# FOC_BOARD.net
KiCad netlist of a schematic drawn in Altium Designer
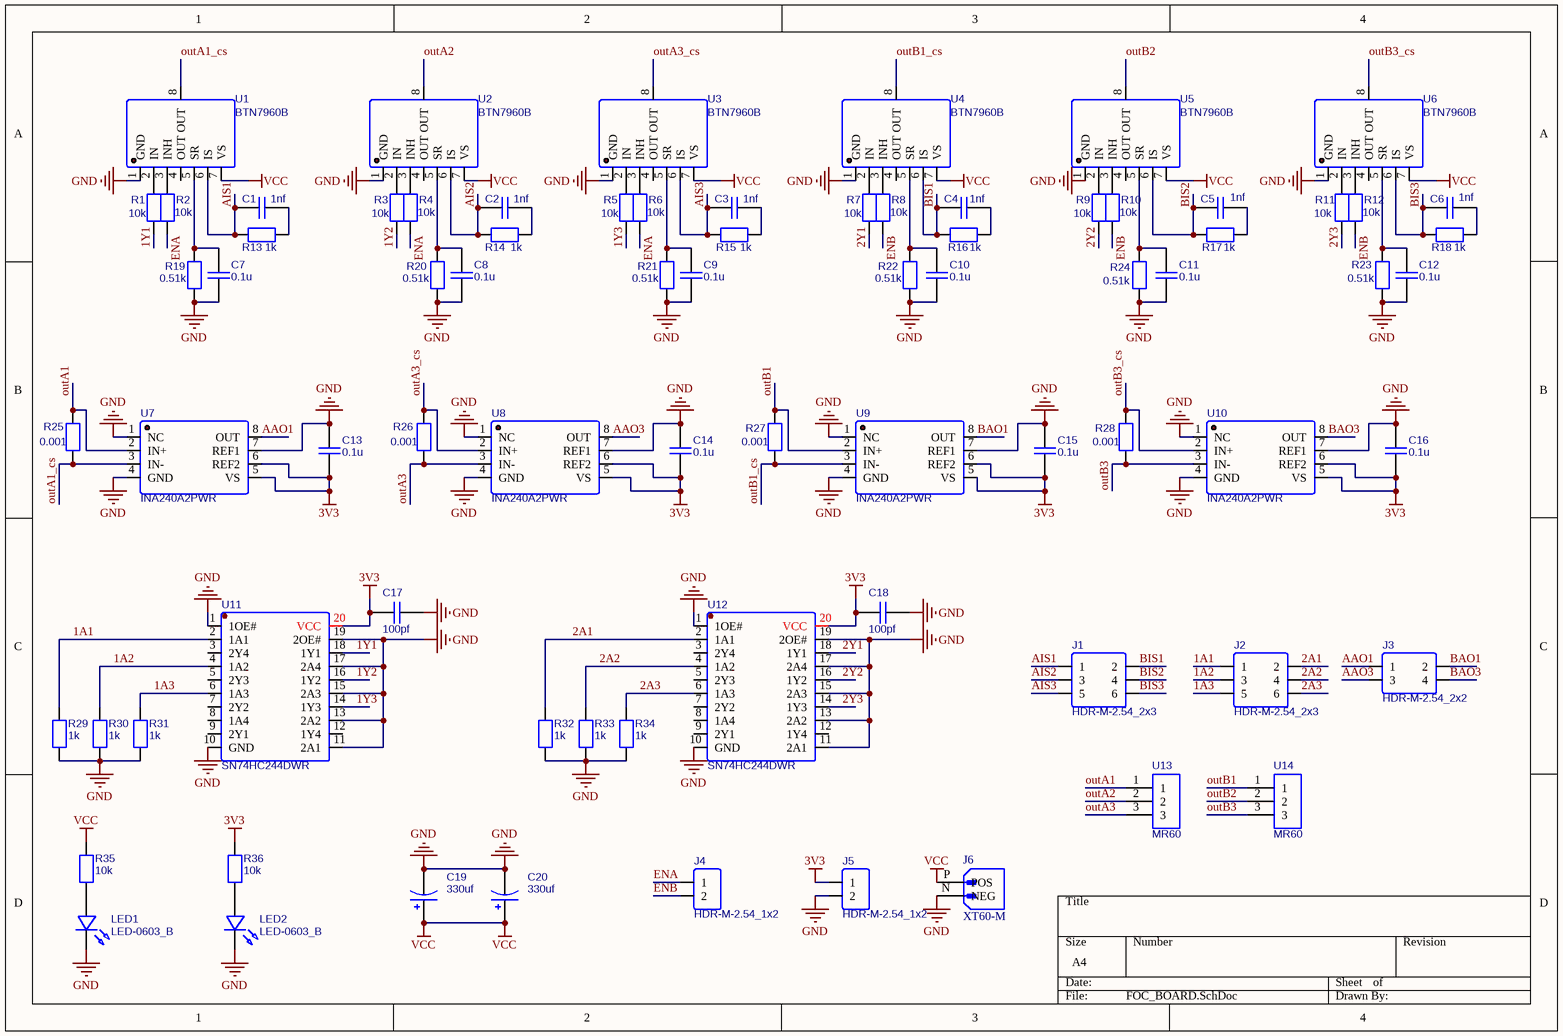
[diagram p0: FOC_BOARD.SchDoc]

(export (version "E")
  (design (tool "Eeschema 10.0.6"))
  (components
    (comp (ref "C1")
      (value "1nf")
      (footprint "C0603")
      (fields (field (name "CONTRIBUTOR") "LCEDA_Lib"))
      (libsource (lib "FOC_BOARD") (part "1nf"))
    )
    (comp (ref "C2")
      (value "1nf")
      (footprint "C0603")
      (fields (field (name "CONTRIBUTOR") "LCEDA_Lib"))
      (libsource (lib "FOC_BOARD") (part "1nf"))
    )
    (comp (ref "C3")
      (value "1nf")
      (footprint "C0603")
      (fields (field (name "CONTRIBUTOR") "LCEDA_Lib"))
      (libsource (lib "FOC_BOARD") (part "1nf"))
    )
    (comp (ref "C4")
      (value "1nf")
      (footprint "C0603")
      (fields (field (name "CONTRIBUTOR") "LCEDA_Lib"))
      (libsource (lib "FOC_BOARD") (part "1nf"))
    )
    (comp (ref "C5")
      (value "1nf")
      (footprint "C0603")
      (fields (field (name "CONTRIBUTOR") "LCEDA_Lib"))
      (libsource (lib "FOC_BOARD") (part "1nf"))
    )
    (comp (ref "C6")
      (value "1nf")
      (footprint "C0603")
      (fields (field (name "CONTRIBUTOR") "LCEDA_Lib"))
      (libsource (lib "FOC_BOARD") (part "1nf"))
    )
    (comp (ref "C7")
      (value "0.1u")
      (footprint "C0603")
      (fields (field (name "CONTRIBUTOR") "LCEDA_Lib"))
      (libsource (lib "FOC_BOARD") (part "0.1u"))
    )
    (comp (ref "C8")
      (value "0.1u")
      (footprint "C0603")
      (fields (field (name "CONTRIBUTOR") "LCEDA_Lib"))
      (libsource (lib "FOC_BOARD") (part "0.1u"))
    )
    (comp (ref "C9")
      (value "0.1u")
      (footprint "C0603")
      (fields (field (name "CONTRIBUTOR") "LCEDA_Lib"))
      (libsource (lib "FOC_BOARD") (part "0.1u"))
    )
    (comp (ref "C10")
      (value "0.1u")
      (footprint "C0603")
      (fields (field (name "CONTRIBUTOR") "LCEDA_Lib"))
      (libsource (lib "FOC_BOARD") (part "0.1u"))
    )
    (comp (ref "C11")
      (value "0.1u")
      (footprint "C0603")
      (fields (field (name "CONTRIBUTOR") "LCEDA_Lib"))
      (libsource (lib "FOC_BOARD") (part "0.1u"))
    )
    (comp (ref "C12")
      (value "0.1u")
      (footprint "C0603")
      (fields (field (name "CONTRIBUTOR") "LCEDA_Lib"))
      (libsource (lib "FOC_BOARD") (part "0.1u"))
    )
    (comp (ref "C13")
      (value "0.1u")
      (footprint "C0603")
      (fields (field (name "CONTRIBUTOR") "LCEDA_Lib"))
      (libsource (lib "FOC_BOARD") (part "0.1u"))
    )
    (comp (ref "C14")
      (value "0.1u")
      (footprint "C0603")
      (fields (field (name "CONTRIBUTOR") "LCEDA_Lib"))
      (libsource (lib "FOC_BOARD") (part "0.1u"))
    )
    (comp (ref "C15")
      (value "0.1u")
      (footprint "C0603")
      (fields (field (name "CONTRIBUTOR") "LCEDA_Lib"))
      (libsource (lib "FOC_BOARD") (part "0.1u"))
    )
    (comp (ref "C16")
      (value "0.1u")
      (footprint "C0603")
      (fields (field (name "CONTRIBUTOR") "LCEDA_Lib"))
      (libsource (lib "FOC_BOARD") (part "0.1u"))
    )
    (comp (ref "C17")
      (value "100pf")
      (footprint "C0603")
      (fields (field (name "CONTRIBUTOR") "LCEDA_Lib"))
      (libsource (lib "FOC_BOARD") (part "100pf"))
    )
    (comp (ref "C18")
      (value "100pf")
      (footprint "C0603")
      (fields (field (name "CONTRIBUTOR") "LCEDA_Lib"))
      (libsource (lib "FOC_BOARD") (part "100pf"))
    )
    (comp (ref "C19")
      (value "330uf")
      (footprint "CAP-T-10*10.5")
      (fields (field (name "CONTRIBUTOR") "LCEDA_Lib"))
      (libsource (lib "FOC_BOARD") (part "330uf"))
    )
    (comp (ref "C20")
      (value "330uf")
      (footprint "CAP-T-10*10.5")
      (fields (field (name "CONTRIBUTOR") "LCEDA_Lib"))
      (libsource (lib "FOC_BOARD") (part "330uf"))
    )
    (comp (ref "J1")
      (value "HDR-M-2.54_2x3")
      (footprint "HDR-M-2.54_2X3")
      (fields (field (name "BOM_SUPPLIER PART") "C65114") (field (name "CONTRIBUTOR") "LCEDA_Lib"))
      (libsource (lib "FOC_BOARD") (part "HDR-M-2.54_2x3"))
    )
    (comp (ref "J2")
      (value "HDR-M-2.54_2x3")
      (footprint "HDR-M-2.54_2X3")
      (fields (field (name "BOM_SUPPLIER PART") "C65114") (field (name "CONTRIBUTOR") "LCEDA_Lib"))
      (libsource (lib "FOC_BOARD") (part "HDR-M-2.54_2x3"))
    )
    (comp (ref "J3")
      (value "HDR-M-2.54_2x2")
      (footprint "HDR-M-2.54_2X2")
      (fields (field (name "BOM_SUPPLIER PART") "C66690") (field (name "CONTRIBUTOR") "LCEDA_Lib"))
      (libsource (lib "FOC_BOARD") (part "HDR-M-2.54_2x2"))
    )
    (comp (ref "J4")
      (value "HDR-M-2.54_1x2")
      (footprint "HDR-M-2.54_1X2")
      (fields (field (name "BOM_SUPPLIER PART") "C124375") (field (name "CONTRIBUTOR") "LCEDA_Lib"))
      (libsource (lib "FOC_BOARD") (part "HDR-M-2.54_1x2"))
    )
    (comp (ref "J5")
      (value "HDR-M-2.54_1x2")
      (footprint "HDR-M-2.54_1X2")
      (fields (field (name "BOM_SUPPLIER PART") "C124375") (field (name "CONTRIBUTOR") "LCEDA_Lib"))
      (libsource (lib "FOC_BOARD") (part "HDR-M-2.54_1x2"))
    )
    (comp (ref "J6")
      (value "XT60-M")
      (footprint "AMASS_XT60-M")
      (description "Plug; DC supply; XT60; male; PIN: 2; for cable; soldered; 30A; 500V")
      (fields (field (name "MF") "AMASS"))
      (libsource (lib "FOC_BOARD") (part "XT60-M"))
    )
    (comp (ref "LED1")
      (value "LED-0603_B")
      (footprint "LED0603_BLUE")
      (fields
        (field (name "BOM_MANUFACTURER PART") "19-217/BHC-ZL1M2RY/3T")
        (field (name "BOM_SUPPLIER PART") "C72041")
        (field (name "CONTRIBUTOR") "LCEDA_01")
      )
      (libsource (lib "FOC_BOARD") (part "LED-0603_B"))
    )
    (comp (ref "LED2")
      (value "LED-0603_B")
      (footprint "LED0603_BLUE")
      (fields
        (field (name "BOM_MANUFACTURER PART") "19-217/BHC-ZL1M2RY/3T")
        (field (name "BOM_SUPPLIER PART") "C72041")
        (field (name "CONTRIBUTOR") "LCEDA_01")
      )
      (libsource (lib "FOC_BOARD") (part "LED-0603_B"))
    )
    (comp (ref "R1")
      (value "10k")
      (footprint "R0603")
      (fields (field (name "CONTRIBUTOR") "LCEDA_Lib"))
      (libsource (lib "FOC_BOARD") (part "10k"))
    )
    (comp (ref "R2")
      (value "10k")
      (footprint "R0603")
      (fields (field (name "CONTRIBUTOR") "LCEDA_Lib"))
      (libsource (lib "FOC_BOARD") (part "10k"))
    )
    (comp (ref "R3")
      (value "10k")
      (footprint "R0603")
      (fields (field (name "CONTRIBUTOR") "LCEDA_Lib"))
      (libsource (lib "FOC_BOARD") (part "10k"))
    )
    (comp (ref "R4")
      (value "10k")
      (footprint "R0603")
      (fields (field (name "CONTRIBUTOR") "LCEDA_Lib"))
      (libsource (lib "FOC_BOARD") (part "10k"))
    )
    (comp (ref "R5")
      (value "10k")
      (footprint "R0603")
      (fields (field (name "CONTRIBUTOR") "LCEDA_Lib"))
      (libsource (lib "FOC_BOARD") (part "10k"))
    )
    (comp (ref "R6")
      (value "10k")
      (footprint "R0603")
      (fields (field (name "CONTRIBUTOR") "LCEDA_Lib"))
      (libsource (lib "FOC_BOARD") (part "10k"))
    )
    (comp (ref "R7")
      (value "10k")
      (footprint "R0603")
      (fields (field (name "CONTRIBUTOR") "LCEDA_Lib"))
      (libsource (lib "FOC_BOARD") (part "10k"))
    )
    (comp (ref "R8")
      (value "10k")
      (footprint "R0603")
      (fields (field (name "CONTRIBUTOR") "LCEDA_Lib"))
      (libsource (lib "FOC_BOARD") (part "10k"))
    )
    (comp (ref "R9")
      (value "10k")
      (footprint "R0603")
      (fields (field (name "CONTRIBUTOR") "LCEDA_Lib"))
      (libsource (lib "FOC_BOARD") (part "10k"))
    )
    (comp (ref "R10")
      (value "10k")
      (footprint "R0603")
      (fields (field (name "CONTRIBUTOR") "LCEDA_Lib"))
      (libsource (lib "FOC_BOARD") (part "10k"))
    )
    (comp (ref "R11")
      (value "10k")
      (footprint "R0603")
      (fields (field (name "CONTRIBUTOR") "LCEDA_Lib"))
      (libsource (lib "FOC_BOARD") (part "10k"))
    )
    (comp (ref "R12")
      (value "10k")
      (footprint "R0603")
      (fields (field (name "CONTRIBUTOR") "LCEDA_Lib"))
      (libsource (lib "FOC_BOARD") (part "10k"))
    )
    (comp (ref "R13")
      (value "1k")
      (footprint "R0603")
      (fields (field (name "CONTRIBUTOR") "LCEDA_Lib"))
      (libsource (lib "FOC_BOARD") (part "1k"))
    )
    (comp (ref "R14")
      (value "1k")
      (footprint "R0603")
      (fields (field (name "CONTRIBUTOR") "LCEDA_Lib"))
      (libsource (lib "FOC_BOARD") (part "1k"))
    )
    (comp (ref "R15")
      (value "1k")
      (footprint "R0603")
      (fields (field (name "CONTRIBUTOR") "LCEDA_Lib"))
      (libsource (lib "FOC_BOARD") (part "1k"))
    )
    (comp (ref "R16")
      (value "1k")
      (footprint "R0603")
      (fields (field (name "CONTRIBUTOR") "LCEDA_Lib"))
      (libsource (lib "FOC_BOARD") (part "1k"))
    )
    (comp (ref "R17")
      (value "1k")
      (footprint "R0603")
      (fields (field (name "CONTRIBUTOR") "LCEDA_Lib"))
      (libsource (lib "FOC_BOARD") (part "1k"))
    )
    (comp (ref "R18")
      (value "1k")
      (footprint "R0603")
      (fields (field (name "CONTRIBUTOR") "LCEDA_Lib"))
      (libsource (lib "FOC_BOARD") (part "1k"))
    )
    (comp (ref "R19")
      (value "0.51k")
      (footprint "R0603")
      (fields (field (name "CONTRIBUTOR") "LCEDA_Lib"))
      (libsource (lib "FOC_BOARD") (part "0.51k"))
    )
    (comp (ref "R20")
      (value "0.51k")
      (footprint "R0603")
      (fields (field (name "CONTRIBUTOR") "LCEDA_Lib"))
      (libsource (lib "FOC_BOARD") (part "0.51k"))
    )
    (comp (ref "R21")
      (value "0.51k")
      (footprint "R0603")
      (fields (field (name "CONTRIBUTOR") "LCEDA_Lib"))
      (libsource (lib "FOC_BOARD") (part "0.51k"))
    )
    (comp (ref "R22")
      (value "0.51k")
      (footprint "R0603")
      (fields (field (name "CONTRIBUTOR") "LCEDA_Lib"))
      (libsource (lib "FOC_BOARD") (part "0.51k"))
    )
    (comp (ref "R23")
      (value "0.51k")
      (footprint "R0603")
      (fields (field (name "CONTRIBUTOR") "LCEDA_Lib"))
      (libsource (lib "FOC_BOARD") (part "0.51k"))
    )
    (comp (ref "R24")
      (value "0.51k")
      (footprint "R0603")
      (fields (field (name "CONTRIBUTOR") "LCEDA_Lib"))
      (libsource (lib "FOC_BOARD") (part "0.51k"))
    )
    (comp (ref "R25")
      (value "0.001")
      (footprint "R2512")
      (fields (field (name "CONTRIBUTOR") "LCEDA_Lib"))
      (libsource (lib "FOC_BOARD") (part "0.001"))
    )
    (comp (ref "R26")
      (value "0.001")
      (footprint "R2512")
      (fields (field (name "CONTRIBUTOR") "LCEDA_Lib"))
      (libsource (lib "FOC_BOARD") (part "0.001"))
    )
    (comp (ref "R27")
      (value "0.001")
      (footprint "R2512")
      (fields (field (name "CONTRIBUTOR") "LCEDA_Lib"))
      (libsource (lib "FOC_BOARD") (part "0.001"))
    )
    (comp (ref "R28")
      (value "0.001")
      (footprint "R2512")
      (fields (field (name "CONTRIBUTOR") "LCEDA_Lib"))
      (libsource (lib "FOC_BOARD") (part "0.001"))
    )
    (comp (ref "R29")
      (value "1k")
      (footprint "R0603")
      (fields (field (name "CONTRIBUTOR") "LCEDA_Lib"))
      (libsource (lib "FOC_BOARD") (part "1k"))
    )
    (comp (ref "R30")
      (value "1k")
      (footprint "R0603")
      (fields (field (name "CONTRIBUTOR") "LCEDA_Lib"))
      (libsource (lib "FOC_BOARD") (part "1k"))
    )
    (comp (ref "R31")
      (value "1k")
      (footprint "R0603")
      (fields (field (name "CONTRIBUTOR") "LCEDA_Lib"))
      (libsource (lib "FOC_BOARD") (part "1k"))
    )
    (comp (ref "R32")
      (value "1k")
      (footprint "R0603")
      (fields (field (name "CONTRIBUTOR") "LCEDA_Lib"))
      (libsource (lib "FOC_BOARD") (part "1k"))
    )
    (comp (ref "R33")
      (value "1k")
      (footprint "R0603")
      (fields (field (name "CONTRIBUTOR") "LCEDA_Lib"))
      (libsource (lib "FOC_BOARD") (part "1k"))
    )
    (comp (ref "R34")
      (value "1k")
      (footprint "R0603")
      (fields (field (name "CONTRIBUTOR") "LCEDA_Lib"))
      (libsource (lib "FOC_BOARD") (part "1k"))
    )
    (comp (ref "R35")
      (value "10k")
      (footprint "R0603")
      (fields (field (name "CONTRIBUTOR") "LCEDA_Lib"))
      (libsource (lib "FOC_BOARD") (part "10k"))
    )
    (comp (ref "R36")
      (value "10k")
      (footprint "R0603")
      (fields (field (name "CONTRIBUTOR") "LCEDA_Lib"))
      (libsource (lib "FOC_BOARD") (part "10k"))
    )
    (comp (ref "U1")
      (value "BTN7960B")
      (footprint "TO-263-7_L10.2-W10.4-P1.27-LS14.4-TL")
      (fields (field (name "BOM_SUPPLIER PART") "C648660") (field (name "CONTRIBUTOR") "LCSC"))
      (libsource (lib "FOC_BOARD") (part "BTN7960B"))
    )
    (comp (ref "U2")
      (value "BTN7960B")
      (footprint "TO-263-7_L10.2-W10.4-P1.27-LS14.4-TL")
      (fields (field (name "BOM_SUPPLIER PART") "C648660") (field (name "CONTRIBUTOR") "LCSC"))
      (libsource (lib "FOC_BOARD") (part "BTN7960B"))
    )
    (comp (ref "U3")
      (value "BTN7960B")
      (footprint "TO-263-7_L10.2-W10.4-P1.27-LS14.4-TL")
      (fields (field (name "BOM_SUPPLIER PART") "C648660") (field (name "CONTRIBUTOR") "LCSC"))
      (libsource (lib "FOC_BOARD") (part "BTN7960B"))
    )
    (comp (ref "U4")
      (value "BTN7960B")
      (footprint "TO-263-7_L10.2-W10.4-P1.27-LS14.4-TL")
      (fields (field (name "BOM_SUPPLIER PART") "C648660") (field (name "CONTRIBUTOR") "LCSC"))
      (libsource (lib "FOC_BOARD") (part "BTN7960B"))
    )
    (comp (ref "U5")
      (value "BTN7960B")
      (footprint "TO-263-7_L10.2-W10.4-P1.27-LS14.4-TL")
      (fields (field (name "BOM_SUPPLIER PART") "C648660") (field (name "CONTRIBUTOR") "LCSC"))
      (libsource (lib "FOC_BOARD") (part "BTN7960B"))
    )
    (comp (ref "U6")
      (value "BTN7960B")
      (footprint "TO-263-7_L10.2-W10.4-P1.27-LS14.4-TL")
      (fields (field (name "BOM_SUPPLIER PART") "C648660") (field (name "CONTRIBUTOR") "LCSC"))
      (libsource (lib "FOC_BOARD") (part "BTN7960B"))
    )
    (comp (ref "U7")
      (value "INA240A2PWR")
      (footprint "TSSOP-8_L4.4-W3.0-P0.65-LS6.4-BL")
      (fields (field (name "BOM_SUPPLIER PART") "C129949") (field (name "CONTRIBUTOR") "LCSC"))
      (libsource (lib "FOC_BOARD") (part "INA240A2PWR"))
    )
    (comp (ref "U8")
      (value "INA240A2PWR")
      (footprint "TSSOP-8_L4.4-W3.0-P0.65-LS6.4-BL")
      (fields (field (name "BOM_SUPPLIER PART") "C129949") (field (name "CONTRIBUTOR") "LCSC"))
      (libsource (lib "FOC_BOARD") (part "INA240A2PWR"))
    )
    (comp (ref "U9")
      (value "INA240A2PWR")
      (footprint "TSSOP-8_L4.4-W3.0-P0.65-LS6.4-BL")
      (fields (field (name "BOM_SUPPLIER PART") "C129949") (field (name "CONTRIBUTOR") "LCSC"))
      (libsource (lib "FOC_BOARD") (part "INA240A2PWR"))
    )
    (comp (ref "U10")
      (value "INA240A2PWR")
      (footprint "TSSOP-8_L4.4-W3.0-P0.65-LS6.4-BL")
      (fields (field (name "BOM_SUPPLIER PART") "C129949") (field (name "CONTRIBUTOR") "LCSC"))
      (libsource (lib "FOC_BOARD") (part "INA240A2PWR"))
    )
    (comp (ref "U11")
      (value "SN74HC244DWR")
      (footprint "SN74HC244DWR")
      (fields
        (field (name "BOM_MANUFACTURER PART") "SN74AHC244DWR")
        (field (name "BOM_SUPPLIER PART") "C7473")
      )
      (libsource (lib "FOC_BOARD") (part "SN74HC244DWR"))
    )
    (comp (ref "U12")
      (value "SN74HC244DWR")
      (footprint "SN74HC244DWR")
      (fields
        (field (name "BOM_MANUFACTURER PART") "SN74AHC244DWR")
        (field (name "BOM_SUPPLIER PART") "C7473")
      )
      (libsource (lib "FOC_BOARD") (part "SN74HC244DWR"))
    )
    (comp (ref "U13")
      (value "MR60")
      (footprint "MR60_F")
      (fields (field (name "CONTRIBUTOR") "zjsxzc217"))
      (libsource (lib "FOC_BOARD") (part "MR60"))
    )
    (comp (ref "U14")
      (value "MR60")
      (footprint "MR60_F")
      (fields (field (name "CONTRIBUTOR") "zjsxzc217"))
      (libsource (lib "FOC_BOARD") (part "MR60"))
    )
  )
  (nets
    (net (code "1") (name "/1A1") (class "Default")
      (node (ref "J2") (pin "1") (pinfunction "1_1") (pintype "passive"))
      (node (ref "R29") (pin "1") (pinfunction "1_1") (pintype "passive"))
      (node (ref "U11") (pin "2") (pinfunction "1A1_2") (pintype "passive"))
    )
    (net (code "2") (name "/1A2") (class "Default")
      (node (ref "J2") (pin "3") (pinfunction "3_3") (pintype "passive"))
      (node (ref "R30") (pin "1") (pinfunction "1_1") (pintype "passive"))
      (node (ref "U11") (pin "4") (pinfunction "1A2_4") (pintype "passive"))
    )
    (net (code "3") (name "/1A3") (class "Default")
      (node (ref "J2") (pin "5") (pinfunction "5_5") (pintype "passive"))
      (node (ref "R31") (pin "1") (pinfunction "1_1") (pintype "passive"))
      (node (ref "U11") (pin "6") (pinfunction "1A3_6") (pintype "passive"))
    )
    (net (code "4") (name "/1Y1") (class "Default")
      (node (ref "R1") (pin "2") (pinfunction "2_2") (pintype "passive"))
      (node (ref "U11") (pin "18") (pinfunction "1Y1_18") (pintype "passive"))
    )
    (net (code "5") (name "/1Y2") (class "Default")
      (node (ref "R3") (pin "2") (pinfunction "2_2") (pintype "passive"))
      (node (ref "U11") (pin "16") (pinfunction "1Y2_16") (pintype "passive"))
    )
    (net (code "6") (name "/1Y3") (class "Default")
      (node (ref "R5") (pin "2") (pinfunction "2_2") (pintype "passive"))
      (node (ref "U11") (pin "14") (pinfunction "1Y3_14") (pintype "passive"))
    )
    (net (code "7") (name "/2A1") (class "Default")
      (node (ref "J2") (pin "2") (pinfunction "2_2") (pintype "passive"))
      (node (ref "R32") (pin "1") (pinfunction "1_1") (pintype "passive"))
      (node (ref "U12") (pin "2") (pinfunction "1A1_2") (pintype "passive"))
    )
    (net (code "8") (name "/2A2") (class "Default")
      (node (ref "J2") (pin "4") (pinfunction "4_4") (pintype "passive"))
      (node (ref "R33") (pin "1") (pinfunction "1_1") (pintype "passive"))
      (node (ref "U12") (pin "4") (pinfunction "1A2_4") (pintype "passive"))
    )
    (net (code "9") (name "/2A3") (class "Default")
      (node (ref "J2") (pin "6") (pinfunction "6_6") (pintype "passive"))
      (node (ref "R34") (pin "1") (pinfunction "1_1") (pintype "passive"))
      (node (ref "U12") (pin "6") (pinfunction "1A3_6") (pintype "passive"))
    )
    (net (code "10") (name "/2Y1") (class "Default")
      (node (ref "R7") (pin "2") (pinfunction "2_2") (pintype "passive"))
      (node (ref "U12") (pin "18") (pinfunction "1Y1_18") (pintype "passive"))
    )
    (net (code "11") (name "/2Y2") (class "Default")
      (node (ref "R9") (pin "2") (pinfunction "2_2") (pintype "passive"))
      (node (ref "U12") (pin "16") (pinfunction "1Y2_16") (pintype "passive"))
    )
    (net (code "12") (name "/2Y3") (class "Default")
      (node (ref "R11") (pin "2") (pinfunction "2_2") (pintype "passive"))
      (node (ref "U12") (pin "14") (pinfunction "1Y3_14") (pintype "passive"))
    )
    (net (code "13") (name "/AAO1") (class "Default")
      (node (ref "J3") (pin "1") (pinfunction "1_1") (pintype "passive"))
      (node (ref "U7") (pin "8") (pinfunction "OUT_8") (pintype "passive"))
    )
    (net (code "14") (name "/AAO3") (class "Default")
      (node (ref "J3") (pin "3") (pinfunction "3_3") (pintype "passive"))
      (node (ref "U8") (pin "8") (pinfunction "OUT_8") (pintype "passive"))
    )
    (net (code "15") (name "/AIS1") (class "Default")
      (node (ref "C1") (pin "1") (pinfunction "1_1") (pintype "passive"))
      (node (ref "J1") (pin "1") (pinfunction "1_1") (pintype "passive"))
      (node (ref "R13") (pin "1") (pinfunction "1_1") (pintype "passive"))
      (node (ref "U1") (pin "6") (pinfunction "IS_6") (pintype "passive"))
    )
    (net (code "16") (name "/AIS2") (class "Default")
      (node (ref "C2") (pin "1") (pinfunction "1_1") (pintype "passive"))
      (node (ref "J1") (pin "3") (pinfunction "3_3") (pintype "passive"))
      (node (ref "R14") (pin "1") (pinfunction "1_1") (pintype "passive"))
      (node (ref "U2") (pin "6") (pinfunction "IS_6") (pintype "passive"))
    )
    (net (code "17") (name "/AIS3") (class "Default")
      (node (ref "C3") (pin "1") (pinfunction "1_1") (pintype "passive"))
      (node (ref "J1") (pin "5") (pinfunction "5_5") (pintype "passive"))
      (node (ref "R15") (pin "1") (pinfunction "1_1") (pintype "passive"))
      (node (ref "U3") (pin "6") (pinfunction "IS_6") (pintype "passive"))
    )
    (net (code "18") (name "/BAO1") (class "Default")
      (node (ref "J3") (pin "2") (pinfunction "2_2") (pintype "passive"))
      (node (ref "U9") (pin "8") (pinfunction "OUT_8") (pintype "passive"))
    )
    (net (code "19") (name "/BAO3") (class "Default")
      (node (ref "J3") (pin "4") (pinfunction "4_4") (pintype "passive"))
      (node (ref "U10") (pin "8") (pinfunction "OUT_8") (pintype "passive"))
    )
    (net (code "20") (name "/BIS1") (class "Default")
      (node (ref "C4") (pin "1") (pinfunction "1_1") (pintype "passive"))
      (node (ref "J1") (pin "2") (pinfunction "2_2") (pintype "passive"))
      (node (ref "R16") (pin "1") (pinfunction "1_1") (pintype "passive"))
      (node (ref "U4") (pin "6") (pinfunction "IS_6") (pintype "passive"))
    )
    (net (code "21") (name "/BIS2") (class "Default")
      (node (ref "C5") (pin "1") (pinfunction "1_1") (pintype "passive"))
      (node (ref "J1") (pin "4") (pinfunction "4_4") (pintype "passive"))
      (node (ref "R17") (pin "1") (pinfunction "1_1") (pintype "passive"))
      (node (ref "U5") (pin "6") (pinfunction "IS_6") (pintype "passive"))
    )
    (net (code "22") (name "/BIS3") (class "Default")
      (node (ref "C6") (pin "1") (pinfunction "1_1") (pintype "passive"))
      (node (ref "J1") (pin "6") (pinfunction "6_6") (pintype "passive"))
      (node (ref "R18") (pin "1") (pinfunction "1_1") (pintype "passive"))
      (node (ref "U6") (pin "6") (pinfunction "IS_6") (pintype "passive"))
    )
    (net (code "23") (name "/ENA") (class "Default")
      (node (ref "J4") (pin "1") (pinfunction "1_1") (pintype "passive"))
      (node (ref "R2") (pin "1") (pinfunction "1_1") (pintype "passive"))
      (node (ref "R4") (pin "1") (pinfunction "1_1") (pintype "passive"))
      (node (ref "R6") (pin "1") (pinfunction "1_1") (pintype "passive"))
    )
    (net (code "24") (name "/ENB") (class "Default")
      (node (ref "J4") (pin "2") (pinfunction "2_2") (pintype "passive"))
      (node (ref "R10") (pin "1") (pinfunction "1_1") (pintype "passive"))
      (node (ref "R12") (pin "1") (pinfunction "1_1") (pintype "passive"))
      (node (ref "R8") (pin "1") (pinfunction "1_1") (pintype "passive"))
    )
    (net (code "25") (name "/outA1") (class "Default")
      (node (ref "R25") (pin "2") (pinfunction "2_2") (pintype "passive"))
      (node (ref "U13") (pin "1") (pinfunction "1_1") (pintype "passive"))
      (node (ref "U7") (pin "2") (pinfunction "IN+_2") (pintype "passive"))
    )
    (net (code "26") (name "/outA1_cs") (class "Default")
      (node (ref "R25") (pin "1") (pinfunction "1_1") (pintype "passive"))
      (node (ref "U1") (pin "8") (pinfunction "OUT_8") (pintype "passive"))
      (node (ref "U7") (pin "3") (pinfunction "IN-_3") (pintype "passive"))
    )
    (net (code "27") (name "/outA2") (class "Default")
      (node (ref "U13") (pin "2") (pinfunction "2_2") (pintype "passive"))
      (node (ref "U2") (pin "8") (pinfunction "OUT_8") (pintype "passive"))
    )
    (net (code "28") (name "/outA3") (class "Default")
      (node (ref "R26") (pin "1") (pinfunction "1_1") (pintype "passive"))
      (node (ref "U13") (pin "3") (pinfunction "3_3") (pintype "passive"))
      (node (ref "U8") (pin "3") (pinfunction "IN-_3") (pintype "passive"))
    )
    (net (code "29") (name "/outA3_cs") (class "Default")
      (node (ref "R26") (pin "2") (pinfunction "2_2") (pintype "passive"))
      (node (ref "U3") (pin "8") (pinfunction "OUT_8") (pintype "passive"))
      (node (ref "U8") (pin "2") (pinfunction "IN+_2") (pintype "passive"))
    )
    (net (code "30") (name "/outB1") (class "Default")
      (node (ref "R27") (pin "2") (pinfunction "2_2") (pintype "passive"))
      (node (ref "U14") (pin "1") (pinfunction "1_1") (pintype "passive"))
      (node (ref "U9") (pin "2") (pinfunction "IN+_2") (pintype "passive"))
    )
    (net (code "31") (name "/outB1_cs") (class "Default")
      (node (ref "R27") (pin "1") (pinfunction "1_1") (pintype "passive"))
      (node (ref "U4") (pin "8") (pinfunction "OUT_8") (pintype "passive"))
      (node (ref "U9") (pin "3") (pinfunction "IN-_3") (pintype "passive"))
    )
    (net (code "32") (name "/outB2") (class "Default")
      (node (ref "U14") (pin "2") (pinfunction "2_2") (pintype "passive"))
      (node (ref "U5") (pin "8") (pinfunction "OUT_8") (pintype "passive"))
    )
    (net (code "33") (name "/outB3") (class "Default")
      (node (ref "R28") (pin "1") (pinfunction "1_1") (pintype "passive"))
      (node (ref "U10") (pin "3") (pinfunction "IN-_3") (pintype "passive"))
      (node (ref "U14") (pin "3") (pinfunction "3_3") (pintype "passive"))
    )
    (net (code "34") (name "/outB3_cs") (class "Default")
      (node (ref "R28") (pin "2") (pinfunction "2_2") (pintype "passive"))
      (node (ref "U10") (pin "2") (pinfunction "IN+_2") (pintype "passive"))
      (node (ref "U6") (pin "8") (pinfunction "OUT_8") (pintype "passive"))
    )
    (net (code "35") (name "3V3") (class "Default")
      (node (ref "C13") (pin "1") (pinfunction "1_1") (pintype "passive"))
      (node (ref "C14") (pin "1") (pinfunction "1_1") (pintype "passive"))
      (node (ref "C15") (pin "1") (pinfunction "1_1") (pintype "passive"))
      (node (ref "C16") (pin "1") (pinfunction "1_1") (pintype "passive"))
      (node (ref "C17") (pin "1") (pinfunction "1_1") (pintype "passive"))
      (node (ref "C18") (pin "1") (pinfunction "1_1") (pintype "passive"))
      (node (ref "J5") (pin "1") (pinfunction "1_1") (pintype "passive"))
      (node (ref "R36") (pin "2") (pinfunction "2_2") (pintype "passive"))
      (node (ref "U10") (pin "5") (pinfunction "VS_5") (pintype "passive"))
      (node (ref "U10") (pin "6") (pinfunction "REF2_6") (pintype "passive"))
      (node (ref "U11") (pin "20") (pinfunction "VCC_20") (pintype "passive"))
      (node (ref "U12") (pin "20") (pinfunction "VCC_20") (pintype "passive"))
      (node (ref "U7") (pin "5") (pinfunction "VS_5") (pintype "passive"))
      (node (ref "U7") (pin "6") (pinfunction "REF2_6") (pintype "passive"))
      (node (ref "U8") (pin "5") (pinfunction "VS_5") (pintype "passive"))
      (node (ref "U8") (pin "6") (pinfunction "REF2_6") (pintype "passive"))
      (node (ref "U9") (pin "5") (pinfunction "VS_5") (pintype "passive"))
      (node (ref "U9") (pin "6") (pinfunction "REF2_6") (pintype "passive"))
    )
    (net (code "36") (name "GND") (class "Default")
      (node (ref "C10") (pin "1") (pinfunction "1_1") (pintype "passive"))
      (node (ref "C11") (pin "1") (pinfunction "1_1") (pintype "passive"))
      (node (ref "C12") (pin "1") (pinfunction "1_1") (pintype "passive"))
      (node (ref "C13") (pin "2") (pinfunction "2_2") (pintype "passive"))
      (node (ref "C14") (pin "2") (pinfunction "2_2") (pintype "passive"))
      (node (ref "C15") (pin "2") (pinfunction "2_2") (pintype "passive"))
      (node (ref "C16") (pin "2") (pinfunction "2_2") (pintype "passive"))
      (node (ref "C17") (pin "2") (pinfunction "2_2") (pintype "passive"))
      (node (ref "C18") (pin "2") (pinfunction "2_2") (pintype "passive"))
      (node (ref "C19") (pin "2") (pinfunction "2_2") (pintype "passive"))
      (node (ref "C20") (pin "2") (pinfunction "2_2") (pintype "passive"))
      (node (ref "C7") (pin "1") (pinfunction "1_1") (pintype "passive"))
      (node (ref "C8") (pin "1") (pinfunction "1_1") (pintype "passive"))
      (node (ref "C9") (pin "1") (pinfunction "1_1") (pintype "passive"))
      (node (ref "J5") (pin "2") (pinfunction "2_2") (pintype "passive"))
      (node (ref "J6") (pin "N") (pinfunction "NEG_N") (pintype "passive"))
      (node (ref "LED1") (pin "2") (pinfunction "2_2") (pintype "passive"))
      (node (ref "LED2") (pin "2") (pinfunction "2_2") (pintype "passive"))
      (node (ref "R19") (pin "1") (pinfunction "1_1") (pintype "passive"))
      (node (ref "R20") (pin "1") (pinfunction "1_1") (pintype "passive"))
      (node (ref "R21") (pin "1") (pinfunction "1_1") (pintype "passive"))
      (node (ref "R22") (pin "1") (pinfunction "1_1") (pintype "passive"))
      (node (ref "R23") (pin "1") (pinfunction "1_1") (pintype "passive"))
      (node (ref "R24") (pin "1") (pinfunction "1_1") (pintype "passive"))
      (node (ref "R29") (pin "2") (pinfunction "2_2") (pintype "passive"))
      (node (ref "R30") (pin "2") (pinfunction "2_2") (pintype "passive"))
      (node (ref "R31") (pin "2") (pinfunction "2_2") (pintype "passive"))
      (node (ref "R32") (pin "2") (pinfunction "2_2") (pintype "passive"))
      (node (ref "R33") (pin "2") (pinfunction "2_2") (pintype "passive"))
      (node (ref "R34") (pin "2") (pinfunction "2_2") (pintype "passive"))
      (node (ref "U1") (pin "1") (pinfunction "GND_1") (pintype "passive"))
      (node (ref "U10") (pin "1") (pinfunction "NC_1") (pintype "passive"))
      (node (ref "U10") (pin "4") (pinfunction "GND_4") (pintype "passive"))
      (node (ref "U10") (pin "7") (pinfunction "REF1_7") (pintype "passive"))
      (node (ref "U11") (pin "1") (pinfunction "1OE#_1") (pintype "passive"))
      (node (ref "U11") (pin "10") (pinfunction "GND_10") (pintype "passive"))
      (node (ref "U11") (pin "11") (pinfunction "2A1_11") (pintype "passive"))
      (node (ref "U11") (pin "13") (pinfunction "2A2_13") (pintype "passive"))
      (node (ref "U11") (pin "15") (pinfunction "2A3_15") (pintype "passive"))
      (node (ref "U11") (pin "17") (pinfunction "2A4_17") (pintype "passive"))
      (node (ref "U11") (pin "19") (pinfunction "2OE#_19") (pintype "passive"))
      (node (ref "U12") (pin "1") (pinfunction "1OE#_1") (pintype "passive"))
      (node (ref "U12") (pin "10") (pinfunction "GND_10") (pintype "passive"))
      (node (ref "U12") (pin "11") (pinfunction "2A1_11") (pintype "passive"))
      (node (ref "U12") (pin "13") (pinfunction "2A2_13") (pintype "passive"))
      (node (ref "U12") (pin "15") (pinfunction "2A3_15") (pintype "passive"))
      (node (ref "U12") (pin "17") (pinfunction "2A4_17") (pintype "passive"))
      (node (ref "U12") (pin "19") (pinfunction "2OE#_19") (pintype "passive"))
      (node (ref "U2") (pin "1") (pinfunction "GND_1") (pintype "passive"))
      (node (ref "U3") (pin "1") (pinfunction "GND_1") (pintype "passive"))
      (node (ref "U4") (pin "1") (pinfunction "GND_1") (pintype "passive"))
      (node (ref "U5") (pin "1") (pinfunction "GND_1") (pintype "passive"))
      (node (ref "U6") (pin "1") (pinfunction "GND_1") (pintype "passive"))
      (node (ref "U7") (pin "1") (pinfunction "NC_1") (pintype "passive"))
      (node (ref "U7") (pin "4") (pinfunction "GND_4") (pintype "passive"))
      (node (ref "U7") (pin "7") (pinfunction "REF1_7") (pintype "passive"))
      (node (ref "U8") (pin "1") (pinfunction "NC_1") (pintype "passive"))
      (node (ref "U8") (pin "4") (pinfunction "GND_4") (pintype "passive"))
      (node (ref "U8") (pin "7") (pinfunction "REF1_7") (pintype "passive"))
      (node (ref "U9") (pin "1") (pinfunction "NC_1") (pintype "passive"))
      (node (ref "U9") (pin "4") (pinfunction "GND_4") (pintype "passive"))
      (node (ref "U9") (pin "7") (pinfunction "REF1_7") (pintype "passive"))
    )
    (net (code "37") (name "Net-(C1-Pad2)") (class "Default")
      (node (ref "C1") (pin "2") (pinfunction "2_2") (pintype "passive"))
      (node (ref "R13") (pin "2") (pinfunction "2_2") (pintype "passive"))
    )
    (net (code "38") (name "Net-(C2-Pad2)") (class "Default")
      (node (ref "C2") (pin "2") (pinfunction "2_2") (pintype "passive"))
      (node (ref "R14") (pin "2") (pinfunction "2_2") (pintype "passive"))
    )
    (net (code "39") (name "Net-(C3-Pad2)") (class "Default")
      (node (ref "C3") (pin "2") (pinfunction "2_2") (pintype "passive"))
      (node (ref "R15") (pin "2") (pinfunction "2_2") (pintype "passive"))
    )
    (net (code "40") (name "Net-(C4-Pad2)") (class "Default")
      (node (ref "C4") (pin "2") (pinfunction "2_2") (pintype "passive"))
      (node (ref "R16") (pin "2") (pinfunction "2_2") (pintype "passive"))
    )
    (net (code "41") (name "Net-(C5-Pad2)") (class "Default")
      (node (ref "C5") (pin "2") (pinfunction "2_2") (pintype "passive"))
      (node (ref "R17") (pin "2") (pinfunction "2_2") (pintype "passive"))
    )
    (net (code "42") (name "Net-(C6-Pad2)") (class "Default")
      (node (ref "C6") (pin "2") (pinfunction "2_2") (pintype "passive"))
      (node (ref "R18") (pin "2") (pinfunction "2_2") (pintype "passive"))
    )
    (net (code "43") (name "Net-(LED1-Pad1)") (class "Default")
      (node (ref "LED1") (pin "1") (pinfunction "1_1") (pintype "passive"))
      (node (ref "R35") (pin "1") (pinfunction "1_1") (pintype "passive"))
    )
    (net (code "44") (name "Net-(LED2-Pad1)") (class "Default")
      (node (ref "LED2") (pin "1") (pinfunction "1_1") (pintype "passive"))
      (node (ref "R36") (pin "1") (pinfunction "1_1") (pintype "passive"))
    )
    (net (code "45") (name "Net-(U1-IN)") (class "Default")
      (node (ref "R1") (pin "1") (pinfunction "1_1") (pintype "passive"))
      (node (ref "U1") (pin "2") (pinfunction "IN_2") (pintype "passive"))
    )
    (net (code "46") (name "Net-(U1-INH)") (class "Default")
      (node (ref "R2") (pin "2") (pinfunction "2_2") (pintype "passive"))
      (node (ref "U1") (pin "3") (pinfunction "INH_3") (pintype "passive"))
    )
    (net (code "47") (name "Net-(U1-SR)") (class "Default")
      (node (ref "C7") (pin "2") (pinfunction "2_2") (pintype "passive"))
      (node (ref "R19") (pin "2") (pinfunction "2_2") (pintype "passive"))
      (node (ref "U1") (pin "5") (pinfunction "SR_5") (pintype "passive"))
    )
    (net (code "48") (name "Net-(U2-IN)") (class "Default")
      (node (ref "R3") (pin "1") (pinfunction "1_1") (pintype "passive"))
      (node (ref "U2") (pin "2") (pinfunction "IN_2") (pintype "passive"))
    )
    (net (code "49") (name "Net-(U2-INH)") (class "Default")
      (node (ref "R4") (pin "2") (pinfunction "2_2") (pintype "passive"))
      (node (ref "U2") (pin "3") (pinfunction "INH_3") (pintype "passive"))
    )
    (net (code "50") (name "Net-(U2-SR)") (class "Default")
      (node (ref "C8") (pin "2") (pinfunction "2_2") (pintype "passive"))
      (node (ref "R20") (pin "2") (pinfunction "2_2") (pintype "passive"))
      (node (ref "U2") (pin "5") (pinfunction "SR_5") (pintype "passive"))
    )
    (net (code "51") (name "Net-(U3-IN)") (class "Default")
      (node (ref "R5") (pin "1") (pinfunction "1_1") (pintype "passive"))
      (node (ref "U3") (pin "2") (pinfunction "IN_2") (pintype "passive"))
    )
    (net (code "52") (name "Net-(U3-INH)") (class "Default")
      (node (ref "R6") (pin "2") (pinfunction "2_2") (pintype "passive"))
      (node (ref "U3") (pin "3") (pinfunction "INH_3") (pintype "passive"))
    )
    (net (code "53") (name "Net-(U3-SR)") (class "Default")
      (node (ref "C9") (pin "2") (pinfunction "2_2") (pintype "passive"))
      (node (ref "R21") (pin "2") (pinfunction "2_2") (pintype "passive"))
      (node (ref "U3") (pin "5") (pinfunction "SR_5") (pintype "passive"))
    )
    (net (code "54") (name "Net-(U4-IN)") (class "Default")
      (node (ref "R7") (pin "1") (pinfunction "1_1") (pintype "passive"))
      (node (ref "U4") (pin "2") (pinfunction "IN_2") (pintype "passive"))
    )
    (net (code "55") (name "Net-(U4-INH)") (class "Default")
      (node (ref "R8") (pin "2") (pinfunction "2_2") (pintype "passive"))
      (node (ref "U4") (pin "3") (pinfunction "INH_3") (pintype "passive"))
    )
    (net (code "56") (name "Net-(U4-SR)") (class "Default")
      (node (ref "C10") (pin "2") (pinfunction "2_2") (pintype "passive"))
      (node (ref "R22") (pin "2") (pinfunction "2_2") (pintype "passive"))
      (node (ref "U4") (pin "5") (pinfunction "SR_5") (pintype "passive"))
    )
    (net (code "57") (name "Net-(U5-IN)") (class "Default")
      (node (ref "R9") (pin "1") (pinfunction "1_1") (pintype "passive"))
      (node (ref "U5") (pin "2") (pinfunction "IN_2") (pintype "passive"))
    )
    (net (code "58") (name "Net-(U5-INH)") (class "Default")
      (node (ref "R10") (pin "2") (pinfunction "2_2") (pintype "passive"))
      (node (ref "U5") (pin "3") (pinfunction "INH_3") (pintype "passive"))
    )
    (net (code "59") (name "Net-(U5-SR)") (class "Default")
      (node (ref "C11") (pin "2") (pinfunction "2_2") (pintype "passive"))
      (node (ref "R24") (pin "2") (pinfunction "2_2") (pintype "passive"))
      (node (ref "U5") (pin "5") (pinfunction "SR_5") (pintype "passive"))
    )
    (net (code "60") (name "Net-(U6-IN)") (class "Default")
      (node (ref "R11") (pin "1") (pinfunction "1_1") (pintype "passive"))
      (node (ref "U6") (pin "2") (pinfunction "IN_2") (pintype "passive"))
    )
    (net (code "61") (name "Net-(U6-INH)") (class "Default")
      (node (ref "R12") (pin "2") (pinfunction "2_2") (pintype "passive"))
      (node (ref "U6") (pin "3") (pinfunction "INH_3") (pintype "passive"))
    )
    (net (code "62") (name "Net-(U6-SR)") (class "Default")
      (node (ref "C12") (pin "2") (pinfunction "2_2") (pintype "passive"))
      (node (ref "R23") (pin "2") (pinfunction "2_2") (pintype "passive"))
      (node (ref "U6") (pin "5") (pinfunction "SR_5") (pintype "passive"))
    )
    (net (code "63") (name "VCC") (class "Default")
      (node (ref "C19") (pin "1") (pinfunction "1_1") (pintype "passive"))
      (node (ref "C20") (pin "1") (pinfunction "1_1") (pintype "passive"))
      (node (ref "J6") (pin "P") (pinfunction "POS_P") (pintype "passive"))
      (node (ref "R35") (pin "2") (pinfunction "2_2") (pintype "passive"))
      (node (ref "U1") (pin "7") (pinfunction "VS_7") (pintype "passive"))
      (node (ref "U2") (pin "7") (pinfunction "VS_7") (pintype "passive"))
      (node (ref "U3") (pin "7") (pinfunction "VS_7") (pintype "passive"))
      (node (ref "U4") (pin "7") (pinfunction "VS_7") (pintype "passive"))
      (node (ref "U5") (pin "7") (pinfunction "VS_7") (pintype "passive"))
      (node (ref "U6") (pin "7") (pinfunction "VS_7") (pintype "passive"))
    )
    (net (code "64") (name "unconnected-(U1-OUT-Pad4)") (class "Default")
      (node (ref "U1") (pin "4") (pinfunction "OUT_4") (pintype "passive"))
    )
    (net (code "65") (name "unconnected-(U2-OUT-Pad4)") (class "Default")
      (node (ref "U2") (pin "4") (pinfunction "OUT_4") (pintype "passive"))
    )
    (net (code "66") (name "unconnected-(U3-OUT-Pad4)") (class "Default")
      (node (ref "U3") (pin "4") (pinfunction "OUT_4") (pintype "passive"))
    )
    (net (code "67") (name "unconnected-(U4-OUT-Pad4)") (class "Default")
      (node (ref "U4") (pin "4") (pinfunction "OUT_4") (pintype "passive"))
    )
    (net (code "68") (name "unconnected-(U5-OUT-Pad4)") (class "Default")
      (node (ref "U5") (pin "4") (pinfunction "OUT_4") (pintype "passive"))
    )
    (net (code "69") (name "unconnected-(U6-OUT-Pad4)") (class "Default")
      (node (ref "U6") (pin "4") (pinfunction "OUT_4") (pintype "passive"))
    )
    (net (code "70") (name "unconnected-(U11-1A4-Pad8)") (class "Default")
      (node (ref "U11") (pin "8") (pinfunction "1A4_8") (pintype "passive"))
    )
    (net (code "71") (name "unconnected-(U11-1Y4-Pad12)") (class "Default")
      (node (ref "U11") (pin "12") (pinfunction "1Y4_12") (pintype "passive"))
    )
    (net (code "72") (name "unconnected-(U11-2Y1-Pad9)") (class "Default")
      (node (ref "U11") (pin "9") (pinfunction "2Y1_9") (pintype "passive"))
    )
    (net (code "73") (name "unconnected-(U11-2Y2-Pad7)") (class "Default")
      (node (ref "U11") (pin "7") (pinfunction "2Y2_7") (pintype "passive"))
    )
    (net (code "74") (name "unconnected-(U11-2Y3-Pad5)") (class "Default")
      (node (ref "U11") (pin "5") (pinfunction "2Y3_5") (pintype "passive"))
    )
    (net (code "75") (name "unconnected-(U11-2Y4-Pad3)") (class "Default")
      (node (ref "U11") (pin "3") (pinfunction "2Y4_3") (pintype "passive"))
    )
    (net (code "76") (name "unconnected-(U12-1A4-Pad8)") (class "Default")
      (node (ref "U12") (pin "8") (pinfunction "1A4_8") (pintype "passive"))
    )
    (net (code "77") (name "unconnected-(U12-1Y4-Pad12)") (class "Default")
      (node (ref "U12") (pin "12") (pinfunction "1Y4_12") (pintype "passive"))
    )
    (net (code "78") (name "unconnected-(U12-2Y1-Pad9)") (class "Default")
      (node (ref "U12") (pin "9") (pinfunction "2Y1_9") (pintype "passive"))
    )
    (net (code "79") (name "unconnected-(U12-2Y2-Pad7)") (class "Default")
      (node (ref "U12") (pin "7") (pinfunction "2Y2_7") (pintype "passive"))
    )
    (net (code "80") (name "unconnected-(U12-2Y3-Pad5)") (class "Default")
      (node (ref "U12") (pin "5") (pinfunction "2Y3_5") (pintype "passive"))
    )
    (net (code "81") (name "unconnected-(U12-2Y4-Pad3)") (class "Default")
      (node (ref "U12") (pin "3") (pinfunction "2Y4_3") (pintype "passive"))
    )
  )
)
